# GNS_902_Carrier_Board.net
KiCad netlist of a schematic drawn in EAGLE
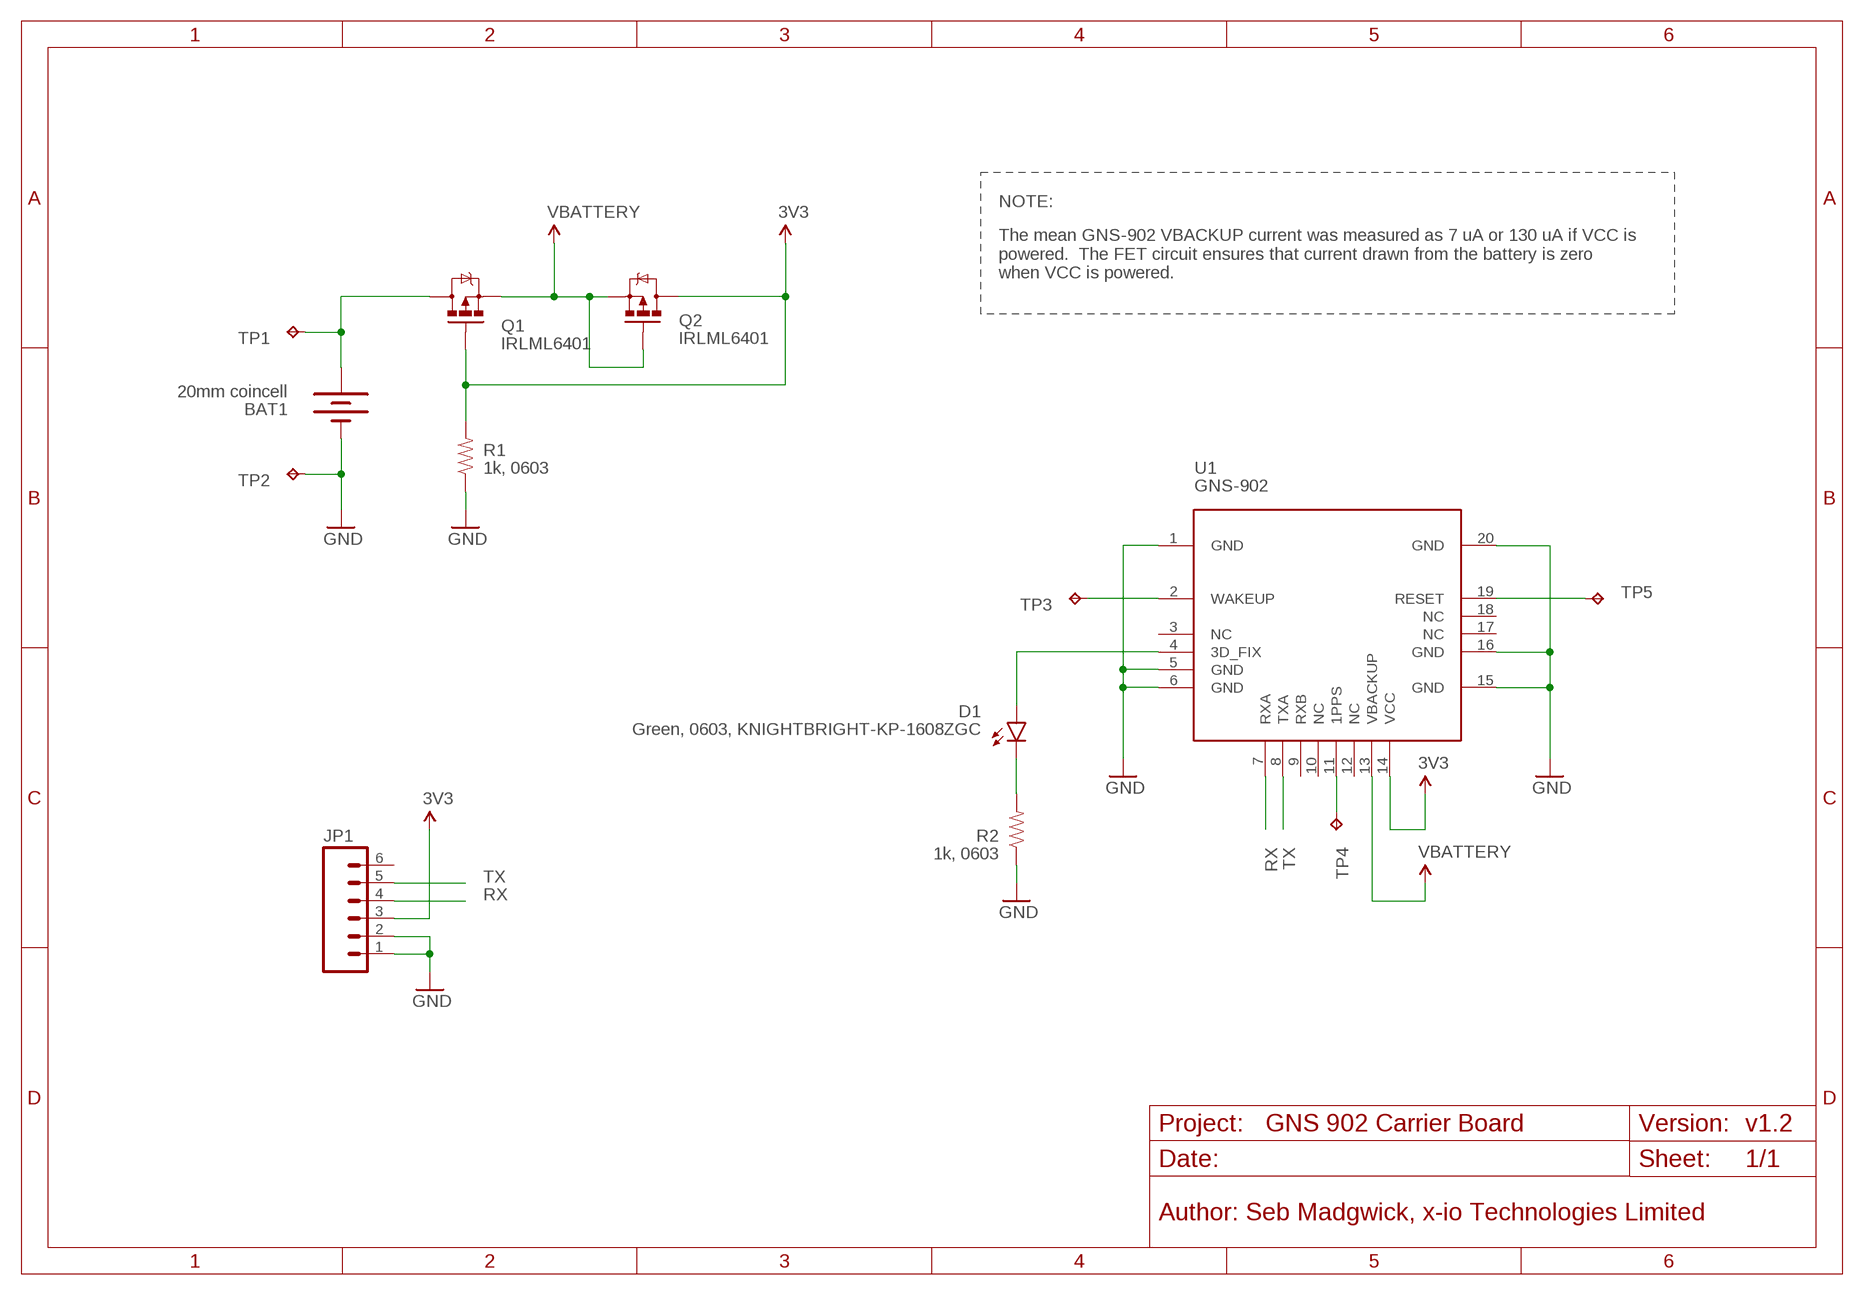
[diagram p0: schematic, sheet 1]

(export (version "E")
  (design (tool "Eeschema 10.0.6"))
  (components
    (comp (ref "BAT1")
      (value "20mm coincell")
      (footprint "eagle-import:BATTCON_20MM_4LEGS")
      (libsource (lib "eagle-import") (part "BATTERY20MM_4LEGS"))
    )
    (comp (ref "D1")
      (value "Green, 0603, KNIGHTBRIGHT-KP-1608ZGC")
      (footprint "eagle-import:LED-0603")
      (libsource (lib "eagle-import") (part "LED0603"))
    )
    (comp (ref "JP1")
      (value "M06NO_SILK_FEMALE_PTH")
      (footprint "eagle-import:1X06_NO_SILK")
      (libsource (lib "eagle-import") (part "M06NO_SILK_FEMALE_PTH"))
    )
    (comp (ref "Q1")
      (value "IRLML6401")
      (footprint "eagle-import:SOT23-3")
      (libsource (lib "eagle-import") (part "MOSFET-PCHANNEL"))
    )
    (comp (ref "Q2")
      (value "IRLML6401")
      (footprint "eagle-import:SOT23-3")
      (libsource (lib "eagle-import") (part "MOSFET-PCHANNEL"))
    )
    (comp (ref "R1")
      (value "1k, 0603")
      (footprint "eagle-import:0603-RES")
      (libsource (lib "eagle-import") (part "RESISTOR0603"))
    )
    (comp (ref "R2")
      (value "1k, 0603")
      (footprint "eagle-import:0603-RES")
      (libsource (lib "eagle-import") (part "RESISTOR0603"))
    )
    (comp (ref "TP1")
      (value "TPTP15R")
      (footprint "eagle-import:TP15R")
      (libsource (lib "eagle-import") (part "TPTP15R"))
    )
    (comp (ref "TP2")
      (value "TPTP15R")
      (footprint "eagle-import:TP15R")
      (libsource (lib "eagle-import") (part "TPTP15R"))
    )
    (comp (ref "TP3")
      (value "TPTP10R")
      (footprint "eagle-import:TP10R")
      (libsource (lib "eagle-import") (part "TPTP10R"))
    )
    (comp (ref "TP4")
      (value "TPTP10R")
      (footprint "eagle-import:TP10R")
      (libsource (lib "eagle-import") (part "TPTP10R"))
    )
    (comp (ref "TP5")
      (value "TPTP10R")
      (footprint "eagle-import:TP10R")
      (libsource (lib "eagle-import") (part "TPTP10R"))
    )
    (comp (ref "U1")
      (value "GNS-902")
      (footprint "eagle-import:GNS-902")
      (libsource (lib "eagle-import") (part "GNS-902"))
    )
  )
  (nets
    (net (code "1") (name "/RX") (class "Default")
      (node (ref "JP1") (pin "4") (pinfunction "4_4") (pintype "passive"))
      (node (ref "U1") (pin "7") (pinfunction "RXA_7") (pintype "bidirectional"))
    )
    (net (code "2") (name "/TX") (class "Default")
      (node (ref "JP1") (pin "5") (pinfunction "5_5") (pintype "passive"))
      (node (ref "U1") (pin "8") (pinfunction "TXA_8") (pintype "bidirectional"))
    )
    (net (code "3") (name "3V3") (class "Default")
      (node (ref "JP1") (pin "3") (pinfunction "3_3") (pintype "passive"))
      (node (ref "Q1") (pin "1") (pinfunction "G_1") (pintype "passive"))
      (node (ref "Q2") (pin "3") (pinfunction "D_3") (pintype "passive"))
      (node (ref "R1") (pin "2") (pinfunction "2_2") (pintype "passive"))
      (node (ref "U1") (pin "14") (pinfunction "VCC_14") (pintype "bidirectional"))
    )
    (net (code "4") (name "GND") (class "Default")
      (node (ref "BAT1") (pin "2") (pinfunction "-_2") (pintype "power_in"))
      (node (ref "JP1") (pin "1") (pinfunction "1_1") (pintype "passive"))
      (node (ref "JP1") (pin "2") (pinfunction "2_2") (pintype "passive"))
      (node (ref "R1") (pin "1") (pinfunction "1_1") (pintype "passive"))
      (node (ref "R2") (pin "1") (pinfunction "1_1") (pintype "passive"))
      (node (ref "TP2") (pin "TP") (pinfunction "TP_TP") (pintype "input"))
      (node (ref "U1") (pin "1") (pinfunction "GND_1") (pintype "bidirectional"))
      (node (ref "U1") (pin "15") (pinfunction "GND_15") (pintype "bidirectional"))
      (node (ref "U1") (pin "16") (pinfunction "GND_16") (pintype "bidirectional"))
      (node (ref "U1") (pin "20") (pinfunction "GND_20") (pintype "bidirectional"))
      (node (ref "U1") (pin "5") (pinfunction "GND_5") (pintype "bidirectional"))
      (node (ref "U1") (pin "6") (pinfunction "GND_6") (pintype "bidirectional"))
    )
    (net (code "5") (name "Net-(BAT1-+)") (class "Default")
      (node (ref "BAT1") (pin "1") (pinfunction "+_1") (pintype "power_in"))
      (node (ref "Q1") (pin "3") (pinfunction "D_3") (pintype "passive"))
      (node (ref "TP1") (pin "TP") (pinfunction "TP_TP") (pintype "input"))
    )
    (net (code "6") (name "Net-(D1-PadC)") (class "Default")
      (node (ref "D1") (pin "C") (pinfunction "C_C") (pintype "passive"))
      (node (ref "R2") (pin "2") (pinfunction "2_2") (pintype "passive"))
    )
    (net (code "7") (name "Net-(U1-1PPS)") (class "Default")
      (node (ref "TP4") (pin "TP") (pinfunction "TP_TP") (pintype "input"))
      (node (ref "U1") (pin "11") (pinfunction "1PPS_11") (pintype "bidirectional"))
    )
    (net (code "8") (name "Net-(U1-3D_FIX)") (class "Default")
      (node (ref "D1") (pin "A") (pinfunction "A_A") (pintype "passive"))
      (node (ref "U1") (pin "4") (pinfunction "3D_FIX_4") (pintype "bidirectional"))
    )
    (net (code "9") (name "Net-(U1-RESET)") (class "Default")
      (node (ref "TP5") (pin "TP") (pinfunction "TP_TP") (pintype "input"))
      (node (ref "U1") (pin "19") (pinfunction "RESET_19") (pintype "bidirectional"))
    )
    (net (code "10") (name "Net-(U1-WAKEUP)") (class "Default")
      (node (ref "TP3") (pin "TP") (pinfunction "TP_TP") (pintype "input"))
      (node (ref "U1") (pin "2") (pinfunction "WAKEUP_2") (pintype "bidirectional"))
    )
    (net (code "11") (name "VBATTERY") (class "Default")
      (node (ref "Q1") (pin "2") (pinfunction "S_2") (pintype "passive"))
      (node (ref "Q2") (pin "1") (pinfunction "G_1") (pintype "passive"))
      (node (ref "Q2") (pin "2") (pinfunction "S_2") (pintype "passive"))
      (node (ref "U1") (pin "13") (pinfunction "VBACKUP_13") (pintype "bidirectional"))
    )
    (net (code "12") (name "unconnected-(JP1-Pad6)") (class "Default")
      (node (ref "JP1") (pin "6") (pinfunction "6_6") (pintype "passive"))
    )
    (net (code "13") (name "unconnected-(U1-NC-Pad3)") (class "Default")
      (node (ref "U1") (pin "3") (pinfunction "NC_3") (pintype "bidirectional"))
    )
    (net (code "14") (name "unconnected-(U1-NC-Pad10)") (class "Default")
      (node (ref "U1") (pin "10") (pinfunction "NC_10") (pintype "bidirectional"))
    )
    (net (code "15") (name "unconnected-(U1-NC-Pad12)") (class "Default")
      (node (ref "U1") (pin "12") (pinfunction "NC_12") (pintype "bidirectional"))
    )
    (net (code "16") (name "unconnected-(U1-NC-Pad17)") (class "Default")
      (node (ref "U1") (pin "17") (pinfunction "NC_17") (pintype "bidirectional"))
    )
    (net (code "17") (name "unconnected-(U1-NC-Pad18)") (class "Default")
      (node (ref "U1") (pin "18") (pinfunction "NC_18") (pintype "bidirectional"))
    )
    (net (code "18") (name "unconnected-(U1-RXB-Pad9)") (class "Default")
      (node (ref "U1") (pin "9") (pinfunction "RXB_9") (pintype "bidirectional"))
    )
  )
)
